# Adafruit_BME680.net
KiCad netlist of a schematic drawn in EAGLE
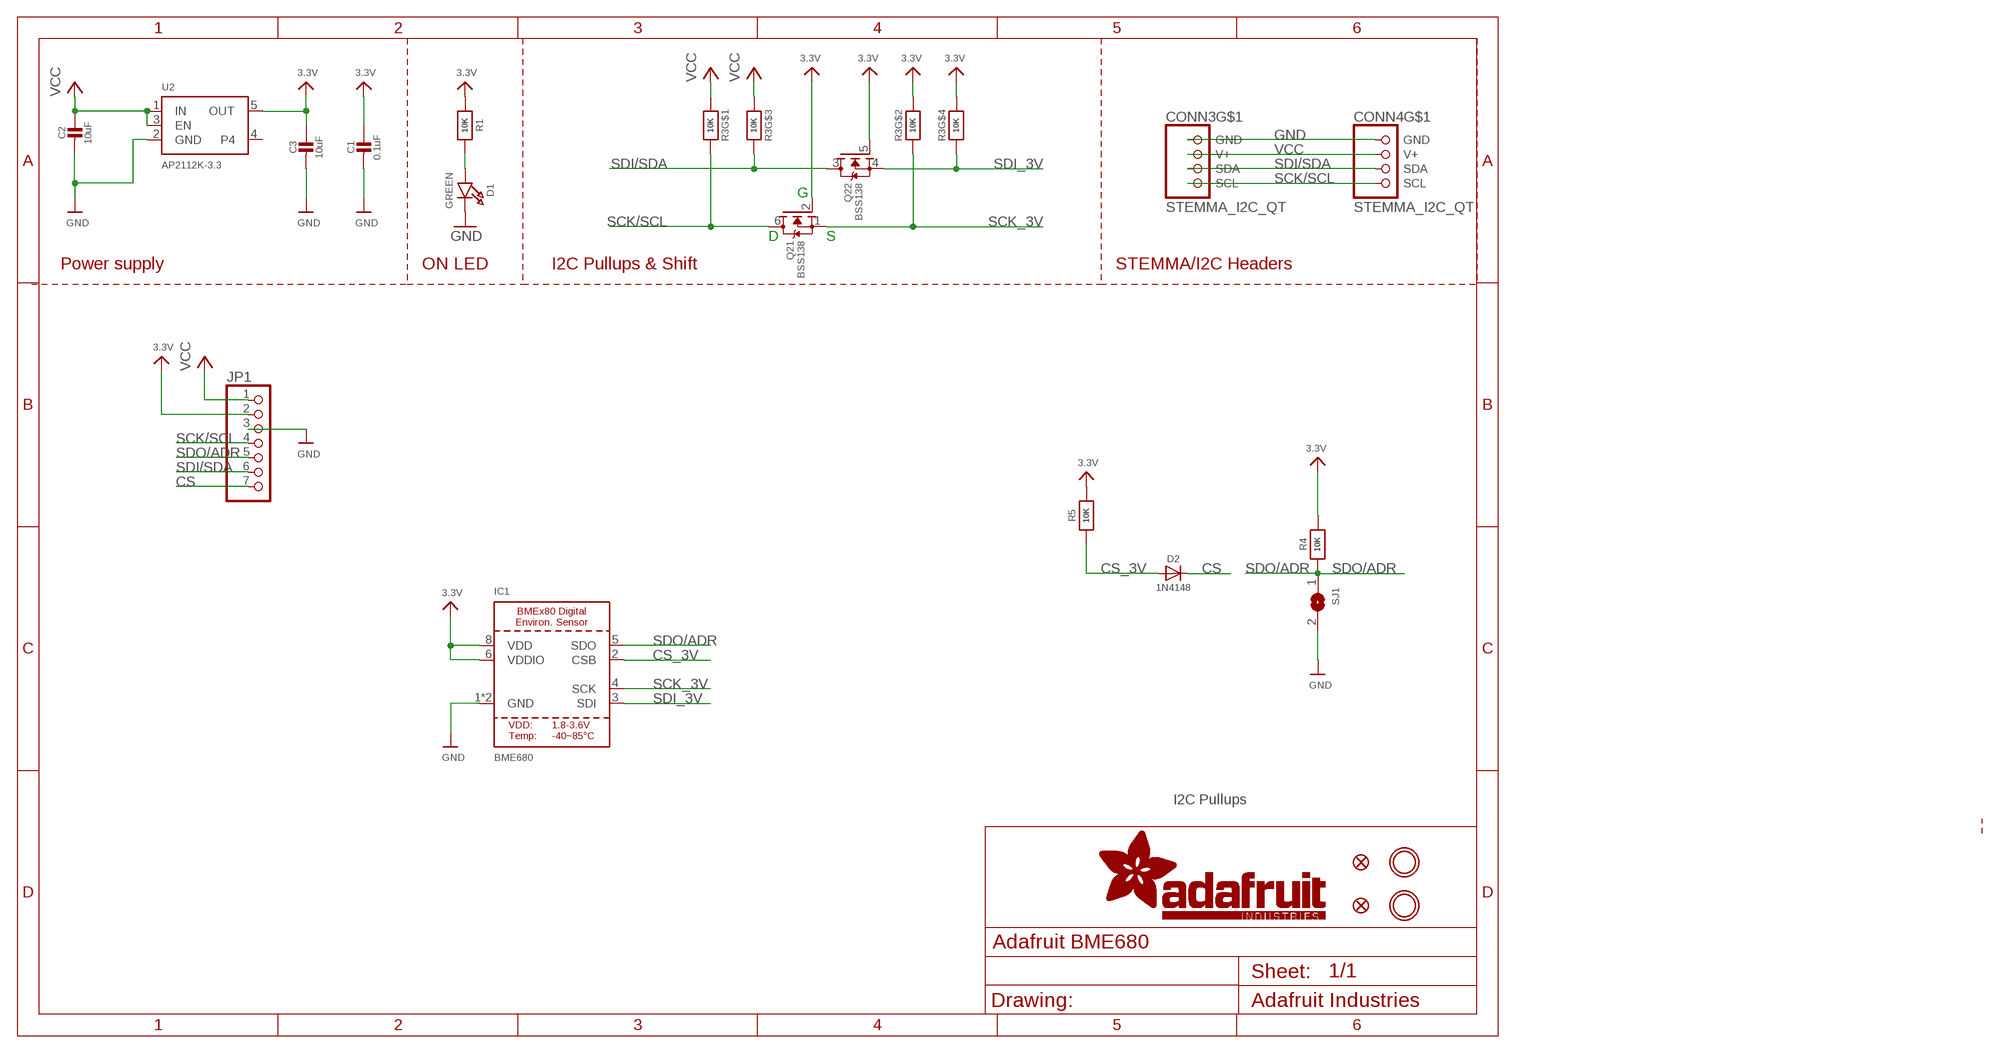
[diagram p0: schematic, sheet 1]

(export (version "E")
  (design (tool "Eeschema 10.0.6"))
  (components
    (comp (ref "C1")
      (value "0.1uF")
      (footprint "eagle-import:0603-NO")
      (libsource (lib "eagle-import") (part "CAP_CERAMIC0603_NO"))
    )
    (comp (ref "C2")
      (value "10uF")
      (footprint "eagle-import:0805-NO")
      (libsource (lib "eagle-import") (part "CAP_CERAMIC0805-NOOUTLINE"))
    )
    (comp (ref "C3")
      (value "10uF")
      (footprint "eagle-import:0805-NO")
      (libsource (lib "eagle-import") (part "CAP_CERAMIC0805-NOOUTLINE"))
    )
    (comp (ref "CONN3")
      (value "STEMMA_I2C_QT")
      (footprint "eagle-import:JST_SH4")
      (libsource (lib "eagle-import") (part "STEMMA_I2C_QT"))
    )
    (comp (ref "CONN4")
      (value "STEMMA_I2C_QT")
      (footprint "eagle-import:JST_SH4")
      (libsource (lib "eagle-import") (part "STEMMA_I2C_QT"))
    )
    (comp (ref "D1")
      (value "GREEN")
      (footprint "eagle-import:CHIPLED_0603_NOOUTLINE")
      (libsource (lib "eagle-import") (part "LED0603_NOOUTLINE"))
    )
    (comp (ref "D2")
      (value "1N4148")
      (footprint "eagle-import:SOD-323")
      (libsource (lib "eagle-import") (part "DIODESOD-323"))
    )
    (comp (ref "FID3")
      (value "FIDUCIAL_1MM")
      (footprint "eagle-import:FIDUCIAL_1MM")
      (libsource (lib "eagle-import") (part "FIDUCIAL_1MM"))
    )
    (comp (ref "FID4")
      (value "FIDUCIAL_1MM")
      (footprint "eagle-import:FIDUCIAL_1MM")
      (libsource (lib "eagle-import") (part "FIDUCIAL_1MM"))
    )
    (comp (ref "IC1")
      (value "BME680")
      (footprint "eagle-import:BME680")
      (libsource (lib "eagle-import") (part "BME680"))
    )
    (comp (ref "JP1")
      (value "HEADER-1X770MIL")
      (footprint "eagle-import:1X07_ROUND_70")
      (libsource (lib "eagle-import") (part "HEADER-1X770MIL"))
    )
    (comp (ref "Q2")
      (value "BSS138")
      (footprint "eagle-import:SOT363")
      (libsource (lib "eagle-import") (part "MOSFET-N_DUAL"))
    )
    (comp (ref "R1")
      (value "10K")
      (footprint "eagle-import:0603-NO")
      (libsource (lib "eagle-import") (part "RESISTOR_0603_NOOUT"))
    )
    (comp (ref "R3")
      (value "10K")
      (footprint "eagle-import:RESPACK_4X0603")
      (libsource (lib "eagle-import") (part "RESISTOR_4PACK"))
    )
    (comp (ref "R4")
      (value "10K")
      (footprint "eagle-import:0603-NO")
      (libsource (lib "eagle-import") (part "RESISTOR_0603_NOOUT"))
    )
    (comp (ref "R5")
      (value "10K")
      (footprint "eagle-import:0603-NO")
      (libsource (lib "eagle-import") (part "RESISTOR_0603_NOOUT"))
    )
    (comp (ref "SJ1")
      (value "SOLDERJUMPER")
      (footprint "eagle-import:SOLDERJUMPER_ARROW_NOPASTE")
      (libsource (lib "eagle-import") (part "SOLDERJUMPER"))
    )
    (comp (ref "U$1")
      (value "MOUNTINGHOLE2.5")
      (footprint "eagle-import:MOUNTINGHOLE_2.5_PLATED")
      (libsource (lib "eagle-import") (part "MOUNTINGHOLE2.5"))
    )
    (comp (ref "U$17")
      (value "MOUNTINGHOLE2.5")
      (footprint "eagle-import:MOUNTINGHOLE_2.5_PLATED")
      (libsource (lib "eagle-import") (part "MOUNTINGHOLE2.5"))
    )
    (comp (ref "U2")
      (value "AP2112K-3.3")
      (footprint "eagle-import:SOT23-5")
      (libsource (lib "eagle-import") (part "VREG_SOT23-5"))
    )
  )
  (nets
    (net (code "1") (name "/CS") (class "Default")
      (node (ref "D2") (pin "C") (pinfunction "C_C") (pintype "passive"))
      (node (ref "JP1") (pin "7") (pinfunction "7_7") (pintype "passive"))
    )
    (net (code "2") (name "/CS_3V") (class "Default")
      (node (ref "D2") (pin "A") (pinfunction "A_A") (pintype "passive"))
      (node (ref "IC1") (pin "2") (pinfunction "CSB_2") (pintype "input"))
      (node (ref "R5") (pin "1") (pinfunction "1_1") (pintype "passive"))
    )
    (net (code "3") (name "/SCK_3V") (class "Default")
      (node (ref "IC1") (pin "4") (pinfunction "SCK_4") (pintype "input"))
      (node (ref "Q2") (pin "1") (pinfunction "S_1") (pintype "bidirectional"))
      (node (ref "R3") (pin "7") (pinfunction "2_7") (pintype "passive"))
    )
    (net (code "4") (name "/SCK{slash}SCL") (class "Default")
      (node (ref "CONN3") (pin "4") (pinfunction "SCL_4") (pintype "passive"))
      (node (ref "CONN4") (pin "4") (pinfunction "SCL_4") (pintype "passive"))
      (node (ref "JP1") (pin "4") (pinfunction "4_4") (pintype "passive"))
      (node (ref "Q2") (pin "6") (pinfunction "D_6") (pintype "bidirectional"))
      (node (ref "R3") (pin "8") (pinfunction "2_8") (pintype "passive"))
    )
    (net (code "5") (name "/SDI_3V") (class "Default")
      (node (ref "IC1") (pin "3") (pinfunction "SDI_3") (pintype "input"))
      (node (ref "Q2") (pin "4") (pinfunction "S_4") (pintype "bidirectional"))
      (node (ref "R3") (pin "5") (pinfunction "2_5") (pintype "passive"))
    )
    (net (code "6") (name "/SDI{slash}SDA") (class "Default")
      (node (ref "CONN3") (pin "3") (pinfunction "SDA_3") (pintype "passive"))
      (node (ref "CONN4") (pin "3") (pinfunction "SDA_3") (pintype "passive"))
      (node (ref "JP1") (pin "6") (pinfunction "6_6") (pintype "passive"))
      (node (ref "Q2") (pin "3") (pinfunction "D_3") (pintype "bidirectional"))
      (node (ref "R3") (pin "6") (pinfunction "2_6") (pintype "passive"))
    )
    (net (code "7") (name "/SDO{slash}ADR") (class "Default")
      (node (ref "IC1") (pin "5") (pinfunction "SDO_5") (pintype "output"))
      (node (ref "JP1") (pin "5") (pinfunction "5_5") (pintype "passive"))
      (node (ref "R4") (pin "1") (pinfunction "1_1") (pintype "passive"))
      (node (ref "SJ1") (pin "1") (pinfunction "1_1") (pintype "passive"))
    )
    (net (code "8") (name "3.3V") (class "Default")
      (node (ref "C1") (pin "1") (pinfunction "1_1") (pintype "passive"))
      (node (ref "C3") (pin "1") (pinfunction "1_1") (pintype "passive"))
      (node (ref "IC1") (pin "6") (pinfunction "VDDIO_6") (pintype "power_in"))
      (node (ref "IC1") (pin "8") (pinfunction "VDD_8") (pintype "power_in"))
      (node (ref "JP1") (pin "2") (pinfunction "2_2") (pintype "passive"))
      (node (ref "Q2") (pin "2") (pinfunction "G_2") (pintype "bidirectional"))
      (node (ref "Q2") (pin "5") (pinfunction "G_5") (pintype "bidirectional"))
      (node (ref "R1") (pin "1") (pinfunction "1_1") (pintype "passive"))
      (node (ref "R3") (pin "2") (pinfunction "1_2") (pintype "passive"))
      (node (ref "R3") (pin "4") (pinfunction "1_4") (pintype "passive"))
      (node (ref "R4") (pin "2") (pinfunction "2_2") (pintype "passive"))
      (node (ref "R5") (pin "2") (pinfunction "2_2") (pintype "passive"))
      (node (ref "U2") (pin "5") (pinfunction "OUT_5") (pintype "power_in"))
    )
    (net (code "9") (name "GND") (class "Default")
      (node (ref "C1") (pin "2") (pinfunction "2_2") (pintype "passive"))
      (node (ref "C2") (pin "2") (pinfunction "2_2") (pintype "passive"))
      (node (ref "C3") (pin "2") (pinfunction "2_2") (pintype "passive"))
      (node (ref "CONN3") (pin "1") (pinfunction "GND_1") (pintype "passive"))
      (node (ref "CONN4") (pin "1") (pinfunction "GND_1") (pintype "passive"))
      (node (ref "D1") (pin "C") (pinfunction "C_C") (pintype "passive"))
      (node (ref "IC1") (pin "1") (pinfunction "GND_1") (pintype "power_in"))
      (node (ref "IC1") (pin "7") (pinfunction "GND_7") (pintype "power_in"))
      (node (ref "JP1") (pin "3") (pinfunction "3_3") (pintype "passive"))
      (node (ref "SJ1") (pin "2") (pinfunction "2_2") (pintype "passive"))
      (node (ref "U2") (pin "2") (pinfunction "GND_2") (pintype "power_in"))
    )
    (net (code "10") (name "Net-(D1-PadA)") (class "Default")
      (node (ref "D1") (pin "A") (pinfunction "A_A") (pintype "passive"))
      (node (ref "R1") (pin "2") (pinfunction "2_2") (pintype "passive"))
    )
    (net (code "11") (name "VCC") (class "Default")
      (node (ref "C2") (pin "1") (pinfunction "1_1") (pintype "passive"))
      (node (ref "CONN3") (pin "2") (pinfunction "V+_2") (pintype "passive"))
      (node (ref "CONN4") (pin "2") (pinfunction "V+_2") (pintype "passive"))
      (node (ref "JP1") (pin "1") (pinfunction "1_1") (pintype "passive"))
      (node (ref "R3") (pin "1") (pinfunction "1_1") (pintype "passive"))
      (node (ref "R3") (pin "3") (pinfunction "1_3") (pintype "passive"))
      (node (ref "U2") (pin "1") (pinfunction "IN_1") (pintype "power_in"))
      (node (ref "U2") (pin "3") (pinfunction "EN_3") (pintype "input"))
    )
    (net (code "12") (name "unconnected-(U2-P4-Pad4)") (class "Default")
      (node (ref "U2") (pin "4") (pinfunction "P4_4") (pintype "bidirectional"))
    )
  )
)
